# VT_8S_LHS_Top_V0_1.net
KiCad netlist of a schematic drawn in Altium Designer
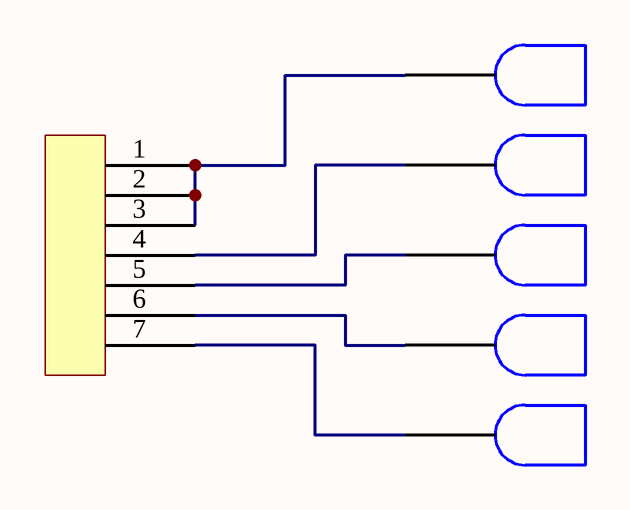
[diagram p0: VT 8S LHS Top V0.1.SchDoc]

(export (version "E")
  (design (tool "Eeschema 10.0.6"))
  (components
    (comp (ref "J1")
      (value "Voltage Tap")
      (footprint "Voltage Tap")
      (libsource (lib "Voltage Taps V0.1") (part "Voltage Tap"))
    )
    (comp (ref "J2")
      (value "Voltage Tap")
      (footprint "Voltage Tap")
      (libsource (lib "Voltage Taps V0.1") (part "Voltage Tap"))
    )
    (comp (ref "J3")
      (value "Voltage Tap")
      (footprint "Voltage Tap")
      (libsource (lib "Voltage Taps V0.1") (part "Voltage Tap"))
    )
    (comp (ref "J4")
      (value "Voltage Tap")
      (footprint "Voltage Tap")
      (libsource (lib "Voltage Taps V0.1") (part "Voltage Tap"))
    )
    (comp (ref "J5")
      (value "Voltage Tap")
      (footprint "Voltage Tap")
      (libsource (lib "Voltage Taps V0.1") (part "Voltage Tap"))
    )
    (comp (ref "J6")
      (value "84953-7-FPC")
      (footprint "84953-7 - FPC")
      (description "FPC Connectors, Flex-to-Board, 7 Position, .039 in [1 mm] Centerline, FPC Side Connector")
      (libsource (lib "TE_Con") (part "84953-7-FPC"))
    )
  )
  (nets
    (net (code "1") (name "Net-(J1-Pad1)") (class "Default")
      (node (ref "J1") (pin "1") (pintype "passive"))
      (node (ref "J6") (pin "1") (pintype "passive"))
      (node (ref "J6") (pin "2") (pintype "passive"))
      (node (ref "J6") (pin "3") (pintype "passive"))
    )
    (net (code "2") (name "Net-(J2-Pad1)") (class "Default")
      (node (ref "J2") (pin "1") (pintype "passive"))
      (node (ref "J6") (pin "4") (pintype "passive"))
    )
    (net (code "3") (name "Net-(J3-Pad1)") (class "Default")
      (node (ref "J3") (pin "1") (pintype "passive"))
      (node (ref "J6") (pin "5") (pintype "passive"))
    )
    (net (code "4") (name "Net-(J4-Pad1)") (class "Default")
      (node (ref "J4") (pin "1") (pintype "passive"))
      (node (ref "J6") (pin "6") (pintype "passive"))
    )
    (net (code "5") (name "Net-(J5-Pad1)") (class "Default")
      (node (ref "J5") (pin "1") (pintype "passive"))
      (node (ref "J6") (pin "7") (pintype "passive"))
    )
  )
)
